# RXTX4.net
KiCad netlist of a schematic drawn in Altium Designer
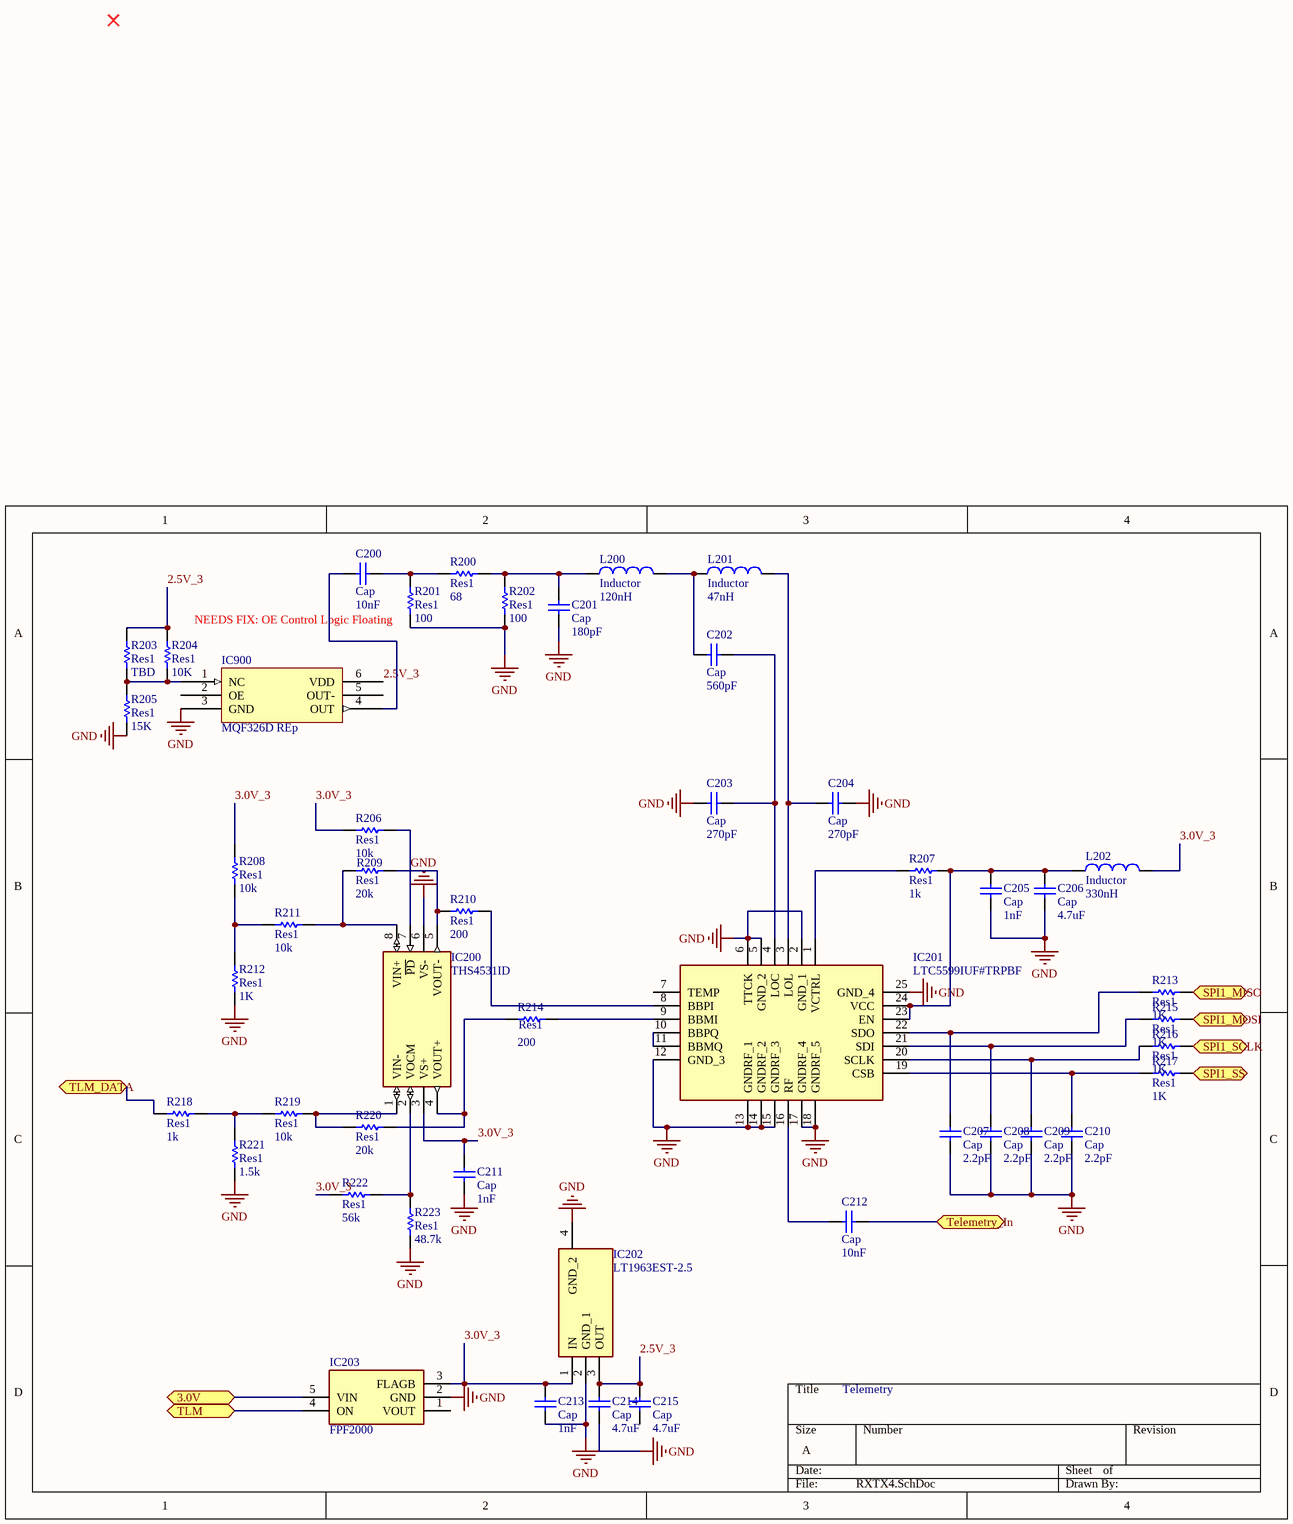
[diagram p0: RXTX4.SchDoc]

(export (version "E")
  (design (tool "Eeschema 10.0.6"))
  (components
    (comp (ref "C200")
      (value "Cap")
      (footprint "0603")
      (description "Capacitor")
      (fields (field (name "ALTIUM_VALUE") "10nF") (field (name "PUBLISHER") "Altium Limited"))
      (libsource (lib "Miscellaneous Devices") (part "Cap"))
    )
    (comp (ref "C201")
      (value "Cap")
      (footprint "0603")
      (description "Capacitor")
      (fields (field (name "ALTIUM_VALUE") "180pF") (field (name "PUBLISHER") "Altium Limited"))
      (libsource (lib "Miscellaneous Devices") (part "Cap"))
    )
    (comp (ref "C202")
      (value "Cap")
      (footprint "0603")
      (description "Capacitor")
      (fields (field (name "ALTIUM_VALUE") "560pF") (field (name "PUBLISHER") "Altium Limited"))
      (libsource (lib "Miscellaneous Devices") (part "Cap"))
    )
    (comp (ref "C203")
      (value "Cap")
      (footprint "0603")
      (description "Capacitor")
      (fields (field (name "ALTIUM_VALUE") "270pF") (field (name "PUBLISHER") "Altium Limited"))
      (libsource (lib "Miscellaneous Devices") (part "Cap"))
    )
    (comp (ref "C204")
      (value "Cap")
      (footprint "0603")
      (description "Capacitor")
      (fields (field (name "ALTIUM_VALUE") "270pF") (field (name "PUBLISHER") "Altium Limited"))
      (libsource (lib "Miscellaneous Devices") (part "Cap"))
    )
    (comp (ref "C205")
      (value "Cap")
      (footprint "0603")
      (description "Capacitor")
      (fields (field (name "ALTIUM_VALUE") "1nF") (field (name "PUBLISHER") "Altium Limited"))
      (libsource (lib "Miscellaneous Devices") (part "Cap"))
    )
    (comp (ref "C206")
      (value "Cap")
      (footprint "0603")
      (description "Capacitor")
      (fields (field (name "ALTIUM_VALUE") "4.7uF") (field (name "PUBLISHER") "Altium Limited"))
      (libsource (lib "Miscellaneous Devices") (part "Cap"))
    )
    (comp (ref "C207")
      (value "Cap")
      (footprint "0603")
      (description "Capacitor")
      (fields (field (name "ALTIUM_VALUE") "2.2pF") (field (name "PUBLISHER") "Altium Limited"))
      (libsource (lib "Miscellaneous Devices") (part "Cap"))
    )
    (comp (ref "C208")
      (value "Cap")
      (footprint "0603")
      (description "Capacitor")
      (fields (field (name "ALTIUM_VALUE") "2.2pF") (field (name "PUBLISHER") "Altium Limited"))
      (libsource (lib "Miscellaneous Devices") (part "Cap"))
    )
    (comp (ref "C209")
      (value "Cap")
      (footprint "0603")
      (description "Capacitor")
      (fields (field (name "ALTIUM_VALUE") "2.2pF") (field (name "PUBLISHER") "Altium Limited"))
      (libsource (lib "Miscellaneous Devices") (part "Cap"))
    )
    (comp (ref "C210")
      (value "Cap")
      (footprint "0603")
      (description "Capacitor")
      (fields (field (name "ALTIUM_VALUE") "2.2pF") (field (name "PUBLISHER") "Altium Limited"))
      (libsource (lib "Miscellaneous Devices") (part "Cap"))
    )
    (comp (ref "C211")
      (value "Cap")
      (footprint "0603")
      (description "Capacitor")
      (fields (field (name "ALTIUM_VALUE") "1nF") (field (name "PUBLISHER") "Altium Limited"))
      (libsource (lib "Miscellaneous Devices") (part "Cap"))
    )
    (comp (ref "C212")
      (value "Cap")
      (footprint "0603")
      (description "Capacitor")
      (fields (field (name "ALTIUM_VALUE") "10nF") (field (name "PUBLISHER") "Altium Limited"))
      (libsource (lib "Miscellaneous Devices") (part "Cap"))
    )
    (comp (ref "C213")
      (value "Cap")
      (footprint "0603")
      (description "Capacitor")
      (fields (field (name "ALTIUM_VALUE") "1nF") (field (name "PUBLISHER") "Altium Limited"))
      (libsource (lib "Miscellaneous Devices") (part "Cap"))
    )
    (comp (ref "C214")
      (value "Cap")
      (footprint "0603")
      (description "Capacitor")
      (fields (field (name "ALTIUM_VALUE") "4.7uF") (field (name "PUBLISHER") "Altium Limited"))
      (libsource (lib "Miscellaneous Devices") (part "Cap"))
    )
    (comp (ref "C215")
      (value "Cap")
      (footprint "0603")
      (description "Capacitor")
      (fields (field (name "ALTIUM_VALUE") "4.7uF") (field (name "PUBLISHER") "Altium Limited"))
      (libsource (lib "Miscellaneous Devices") (part "Cap"))
    )
    (comp (ref "IC200")
      (value "THS4531ID")
      (footprint "SamacSys:SOIC127P600X175-8N")
      (description "Integrated Circuit")
      (fields (field (name "MOUSER PART NUMBER") "595-THS4531ID") (field (name "RS PART NUMBER") "7741408P"))
      (libsource (lib "*") (part "THS4531ID"))
    )
    (comp (ref "IC201")
      (value "LTC5599IUF#TRPBF")
      (footprint "SamacSys:QFN50P400X400X80-25N-D")
      (description "Integrated Circuit")
      (fields (field (name "MOUSER PART NUMBER") "584-LTC5599IUF#TRPBF"))
      (libsource (lib "*") (part "LTC5599IUF#TRPBF"))
    )
    (comp (ref "IC202")
      (value "LT1963EST-2.5")
      (footprint "SamacSys:SOT230P700X180-4N")
      (description "Integrated Circuit")
      (fields (field (name "MOUSER PART NUMBER") "584-LT1963EST-2.5"))
      (libsource (lib "*") (part "LT1963EST-2.5"))
    )
    (comp (ref "IC203")
      (value "FPF2000")
      (footprint "SamacSys:SOT65P210X110-5N")
      (description "Integrated Circuit")
      (fields (field (name "MOUSER PART NUMBER") "512-FPF2000") (field (name "RS PART NUMBER") "6709942P"))
      (libsource (lib "*") (part "FPF2000"))
    )
    (comp (ref "IC900")
      (value "MQF326D REp")
      (footprint "RXTX_PcbLib1:MQF326D")
      (libsource (lib "MQF326D_REP") (part "Component_1"))
    )
    (comp (ref "L200")
      (value "Inductor")
      (footprint "0603")
      (fields (field (name "ALTIUM_VALUE") "120nH") (field (name "PUBLISHER") "Altium Limited"))
      (libsource (lib "Miscellaneous Devices") (part "Inductor"))
    )
    (comp (ref "L201")
      (value "Inductor")
      (footprint "0603")
      (fields (field (name "ALTIUM_VALUE") "47nH") (field (name "PUBLISHER") "Altium Limited"))
      (libsource (lib "Miscellaneous Devices") (part "Inductor"))
    )
    (comp (ref "L202")
      (value "Inductor")
      (footprint "0603")
      (fields (field (name "ALTIUM_VALUE") "330nH") (field (name "PUBLISHER") "Altium Limited"))
      (libsource (lib "Miscellaneous Devices") (part "Inductor"))
    )
    (comp (ref "R200")
      (value "Res1")
      (footprint "0603")
      (description "Resistor")
      (fields (field (name "ALTIUM_VALUE") "68") (field (name "PUBLISHER") "Altium Limited"))
      (libsource (lib "Miscellaneous Devices") (part "Res1"))
    )
    (comp (ref "R201")
      (value "Res1")
      (footprint "0603")
      (description "Resistor")
      (fields (field (name "ALTIUM_VALUE") "100") (field (name "PUBLISHER") "Altium Limited"))
      (libsource (lib "Miscellaneous Devices") (part "Res1"))
    )
    (comp (ref "R202")
      (value "Res1")
      (footprint "0603")
      (description "Resistor")
      (fields (field (name "ALTIUM_VALUE") "100") (field (name "PUBLISHER") "Altium Limited"))
      (libsource (lib "Miscellaneous Devices") (part "Res1"))
    )
    (comp (ref "R203")
      (value "Res1")
      (footprint "0603")
      (description "Resistor")
      (fields (field (name "ALTIUM_VALUE") "TBD") (field (name "PUBLISHER") "Altium Limited"))
      (libsource (lib "Miscellaneous Devices") (part "Res1"))
    )
    (comp (ref "R204")
      (value "Res1")
      (footprint "0603")
      (description "Resistor")
      (fields (field (name "ALTIUM_VALUE") "10K") (field (name "PUBLISHER") "Altium Limited"))
      (libsource (lib "Miscellaneous Devices") (part "Res1"))
    )
    (comp (ref "R205")
      (value "Res1")
      (footprint "0603")
      (description "Resistor")
      (fields (field (name "ALTIUM_VALUE") "15K") (field (name "PUBLISHER") "Altium Limited"))
      (libsource (lib "Miscellaneous Devices") (part "Res1"))
    )
    (comp (ref "R206")
      (value "Res1")
      (footprint "0603")
      (description "Resistor")
      (fields (field (name "ALTIUM_VALUE") "10k") (field (name "PUBLISHER") "Altium Limited"))
      (libsource (lib "Miscellaneous Devices") (part "Res1"))
    )
    (comp (ref "R207")
      (value "Res1")
      (footprint "0603")
      (description "Resistor")
      (fields (field (name "ALTIUM_VALUE") "1k") (field (name "PUBLISHER") "Altium Limited"))
      (libsource (lib "Miscellaneous Devices") (part "Res1"))
    )
    (comp (ref "R208")
      (value "Res1")
      (footprint "0603")
      (description "Resistor")
      (fields (field (name "ALTIUM_VALUE") "10k") (field (name "PUBLISHER") "Altium Limited"))
      (libsource (lib "Miscellaneous Devices") (part "Res1"))
    )
    (comp (ref "R209")
      (value "Res1")
      (footprint "0603")
      (description "Resistor")
      (fields (field (name "ALTIUM_VALUE") "20k") (field (name "PUBLISHER") "Altium Limited"))
      (libsource (lib "Miscellaneous Devices") (part "Res1"))
    )
    (comp (ref "R210")
      (value "Res1")
      (footprint "0603")
      (description "Resistor")
      (fields (field (name "ALTIUM_VALUE") "200") (field (name "PUBLISHER") "Altium Limited"))
      (libsource (lib "Miscellaneous Devices") (part "Res1"))
    )
    (comp (ref "R211")
      (value "Res1")
      (footprint "0603")
      (description "Resistor")
      (fields (field (name "ALTIUM_VALUE") "10k") (field (name "PUBLISHER") "Altium Limited"))
      (libsource (lib "Miscellaneous Devices") (part "Res1"))
    )
    (comp (ref "R212")
      (value "Res1")
      (footprint "0603")
      (description "Resistor")
      (fields (field (name "ALTIUM_VALUE") "1K") (field (name "PUBLISHER") "Altium Limited"))
      (libsource (lib "Miscellaneous Devices") (part "Res1"))
    )
    (comp (ref "R213")
      (value "Res1")
      (footprint "0603")
      (description "Resistor")
      (fields (field (name "ALTIUM_VALUE") "1K") (field (name "PUBLISHER") "Altium Limited"))
      (libsource (lib "Miscellaneous Devices") (part "Res1"))
    )
    (comp (ref "R214")
      (value "Res1")
      (footprint "0603")
      (description "Resistor")
      (fields (field (name "ALTIUM_VALUE") "200") (field (name "PUBLISHER") "Altium Limited"))
      (libsource (lib "Miscellaneous Devices") (part "Res1"))
    )
    (comp (ref "R215")
      (value "Res1")
      (footprint "0603")
      (description "Resistor")
      (fields (field (name "ALTIUM_VALUE") "1K") (field (name "PUBLISHER") "Altium Limited"))
      (libsource (lib "Miscellaneous Devices") (part "Res1"))
    )
    (comp (ref "R216")
      (value "Res1")
      (footprint "0603")
      (description "Resistor")
      (fields (field (name "ALTIUM_VALUE") "1K") (field (name "PUBLISHER") "Altium Limited"))
      (libsource (lib "Miscellaneous Devices") (part "Res1"))
    )
    (comp (ref "R217")
      (value "Res1")
      (footprint "0603")
      (description "Resistor")
      (fields (field (name "ALTIUM_VALUE") "1K") (field (name "PUBLISHER") "Altium Limited"))
      (libsource (lib "Miscellaneous Devices") (part "Res1"))
    )
    (comp (ref "R218")
      (value "Res1")
      (footprint "0603")
      (description "Resistor")
      (fields (field (name "ALTIUM_VALUE") "1k") (field (name "PUBLISHER") "Altium Limited"))
      (libsource (lib "Miscellaneous Devices") (part "Res1"))
    )
    (comp (ref "R219")
      (value "Res1")
      (footprint "0603")
      (description "Resistor")
      (fields (field (name "ALTIUM_VALUE") "10k") (field (name "PUBLISHER") "Altium Limited"))
      (libsource (lib "Miscellaneous Devices") (part "Res1"))
    )
    (comp (ref "R220")
      (value "Res1")
      (footprint "0603")
      (description "Resistor")
      (fields (field (name "ALTIUM_VALUE") "20k") (field (name "PUBLISHER") "Altium Limited"))
      (libsource (lib "Miscellaneous Devices") (part "Res1"))
    )
    (comp (ref "R221")
      (value "Res1")
      (footprint "0603")
      (description "Resistor")
      (fields (field (name "ALTIUM_VALUE") "1.5k") (field (name "PUBLISHER") "Altium Limited"))
      (libsource (lib "Miscellaneous Devices") (part "Res1"))
    )
    (comp (ref "R222")
      (value "Res1")
      (footprint "0603")
      (description "Resistor")
      (fields (field (name "ALTIUM_VALUE") "56k") (field (name "PUBLISHER") "Altium Limited"))
      (libsource (lib "Miscellaneous Devices") (part "Res1"))
    )
    (comp (ref "R223")
      (value "Res1")
      (footprint "0603")
      (description "Resistor")
      (fields (field (name "ALTIUM_VALUE") "48.7k") (field (name "PUBLISHER") "Altium Limited"))
      (libsource (lib "Miscellaneous Devices") (part "Res1"))
    )
  )
  (nets
    (net (code "1") (name "/2.5V_3") (class "Default")
      (node (ref "C214") (pin "1") (pinfunction "1_1") (pintype "passive"))
      (node (ref "C215") (pin "1") (pinfunction "1_1") (pintype "passive"))
      (node (ref "IC202") (pin "3") (pinfunction "OUT_3") (pintype "passive"))
      (node (ref "IC900") (pin "6") (pinfunction "VDD_6") (pintype "power_in"))
      (node (ref "R203") (pin "2") (pinfunction "2_2") (pintype "passive"))
      (node (ref "R204") (pin "2") (pinfunction "2_2") (pintype "passive"))
    )
    (net (code "2") (name "/3.0V") (class "Default")
      (node (ref "IC203") (pin "5") (pinfunction "VIN_5") (pintype "passive"))
    )
    (net (code "3") (name "/3.0V_3") (class "Default")
      (node (ref "C211") (pin "1") (pinfunction "1_1") (pintype "passive"))
      (node (ref "C213") (pin "1") (pinfunction "1_1") (pintype "passive"))
      (node (ref "IC200") (pin "3") (pinfunction "VS+_3") (pintype "power_in"))
      (node (ref "IC202") (pin "1") (pinfunction "IN_1") (pintype "passive"))
      (node (ref "IC203") (pin "3") (pinfunction "FLAGB_3") (pintype "passive"))
      (node (ref "L202") (pin "2") (pinfunction "2_2") (pintype "passive"))
      (node (ref "R206") (pin "1") (pinfunction "1_1") (pintype "passive"))
      (node (ref "R208") (pin "1") (pinfunction "1_1") (pintype "passive"))
      (node (ref "R222") (pin "1") (pinfunction "1_1") (pintype "passive"))
    )
    (net (code "4") (name "/SPI1_MISO") (class "Default")
      (node (ref "R213") (pin "2") (pinfunction "2_2") (pintype "passive"))
    )
    (net (code "5") (name "/SPI1_MOSI") (class "Default")
      (node (ref "R215") (pin "2") (pinfunction "2_2") (pintype "passive"))
    )
    (net (code "6") (name "/SPI1_SCLK") (class "Default")
      (node (ref "R216") (pin "2") (pinfunction "2_2") (pintype "passive"))
    )
    (net (code "7") (name "/SPI1_SS") (class "Default")
      (node (ref "R217") (pin "2") (pinfunction "2_2") (pintype "passive"))
    )
    (net (code "8") (name "/TLM") (class "Default")
      (node (ref "IC203") (pin "4") (pinfunction "ON_4") (pintype "passive"))
    )
    (net (code "9") (name "/TLM_DATA") (class "Default")
      (node (ref "R218") (pin "1") (pinfunction "1_1") (pintype "passive"))
    )
    (net (code "10") (name "/Telemetry_In") (class "Default")
      (node (ref "C212") (pin "2") (pinfunction "2_2") (pintype "passive"))
    )
    (net (code "11") (name "GND") (class "Default")
      (node (ref "C201") (pin "1") (pinfunction "1_1") (pintype "passive"))
      (node (ref "C203") (pin "2") (pinfunction "2_2") (pintype "passive"))
      (node (ref "C204") (pin "1") (pinfunction "1_1") (pintype "passive"))
      (node (ref "C205") (pin "2") (pinfunction "2_2") (pintype "passive"))
      (node (ref "C206") (pin "2") (pinfunction "2_2") (pintype "passive"))
      (node (ref "C207") (pin "2") (pinfunction "2_2") (pintype "passive"))
      (node (ref "C208") (pin "2") (pinfunction "2_2") (pintype "passive"))
      (node (ref "C209") (pin "2") (pinfunction "2_2") (pintype "passive"))
      (node (ref "C210") (pin "2") (pinfunction "2_2") (pintype "passive"))
      (node (ref "C211") (pin "2") (pinfunction "2_2") (pintype "passive"))
      (node (ref "C213") (pin "2") (pinfunction "2_2") (pintype "passive"))
      (node (ref "C214") (pin "2") (pinfunction "2_2") (pintype "passive"))
      (node (ref "IC200") (pin "6") (pinfunction "VS-_6") (pintype "power_in"))
      (node (ref "IC201") (pin "12") (pinfunction "GND_3_12") (pintype "passive"))
      (node (ref "IC201") (pin "13") (pinfunction "GNDRF_1_13") (pintype "passive"))
      (node (ref "IC201") (pin "14") (pinfunction "GNDRF_2_14") (pintype "passive"))
      (node (ref "IC201") (pin "15") (pinfunction "GNDRF_3_15") (pintype "passive"))
      (node (ref "IC201") (pin "17") (pinfunction "GNDRF_4_17") (pintype "passive"))
      (node (ref "IC201") (pin "18") (pinfunction "GNDRF_5_18") (pintype "passive"))
      (node (ref "IC201") (pin "2") (pinfunction "GND_1_2") (pintype "passive"))
      (node (ref "IC201") (pin "25") (pinfunction "GND_4_25") (pintype "passive"))
      (node (ref "IC201") (pin "5") (pinfunction "GND_2_5") (pintype "passive"))
      (node (ref "IC201") (pin "6") (pinfunction "TTCK_6") (pintype "passive"))
      (node (ref "IC202") (pin "2") (pinfunction "GND_1_2") (pintype "passive"))
      (node (ref "IC202") (pin "4") (pinfunction "GND_2_4") (pintype "passive"))
      (node (ref "IC203") (pin "2") (pinfunction "GND_2") (pintype "passive"))
      (node (ref "IC900") (pin "3") (pinfunction "GND_3") (pintype "power_in"))
      (node (ref "R201") (pin "1") (pinfunction "1_1") (pintype "passive"))
      (node (ref "R202") (pin "2") (pinfunction "2_2") (pintype "passive"))
      (node (ref "R205") (pin "1") (pinfunction "1_1") (pintype "passive"))
      (node (ref "R212") (pin "2") (pinfunction "2_2") (pintype "passive"))
      (node (ref "R221") (pin "1") (pinfunction "1_1") (pintype "passive"))
      (node (ref "R223") (pin "1") (pinfunction "1_1") (pintype "passive"))
    )
    (net (code "12") (name "Net-(C200-Pad2)") (class "Default")
      (node (ref "C200") (pin "2") (pinfunction "2_2") (pintype "passive"))
      (node (ref "R200") (pin "2") (pinfunction "2_2") (pintype "passive"))
      (node (ref "R201") (pin "2") (pinfunction "2_2") (pintype "passive"))
    )
    (net (code "13") (name "Net-(C201-Pad2)") (class "Default")
      (node (ref "C201") (pin "2") (pinfunction "2_2") (pintype "passive"))
      (node (ref "L200") (pin "1") (pinfunction "1_1") (pintype "passive"))
      (node (ref "R200") (pin "1") (pinfunction "1_1") (pintype "passive"))
      (node (ref "R202") (pin "1") (pinfunction "1_1") (pintype "passive"))
    )
    (net (code "14") (name "Net-(C202-Pad2)") (class "Default")
      (node (ref "C202") (pin "2") (pinfunction "2_2") (pintype "passive"))
      (node (ref "L200") (pin "2") (pinfunction "2_2") (pintype "passive"))
      (node (ref "L201") (pin "1") (pinfunction "1_1") (pintype "passive"))
    )
    (net (code "15") (name "Net-(IC200-VIN+)") (class "Default")
      (node (ref "IC200") (pin "8") (pinfunction "VIN+_8") (pintype "bidirectional"))
      (node (ref "R209") (pin "1") (pinfunction "1_1") (pintype "passive"))
      (node (ref "R211") (pin "2") (pinfunction "2_2") (pintype "passive"))
    )
    (net (code "16") (name "Net-(IC200-VIN-)") (class "Default")
      (node (ref "IC200") (pin "1") (pinfunction "VIN-_1") (pintype "bidirectional"))
      (node (ref "R219") (pin "2") (pinfunction "2_2") (pintype "passive"))
      (node (ref "R220") (pin "1") (pinfunction "1_1") (pintype "passive"))
    )
    (net (code "17") (name "Net-(IC200-VOCM)") (class "Default")
      (node (ref "IC200") (pin "2") (pinfunction "VOCM_2") (pintype "bidirectional"))
      (node (ref "R222") (pin "2") (pinfunction "2_2") (pintype "passive"))
      (node (ref "R223") (pin "2") (pinfunction "2_2") (pintype "passive"))
    )
    (net (code "18") (name "Net-(IC200-VOUT+)") (class "Default")
      (node (ref "IC200") (pin "4") (pinfunction "VOUT+_4") (pintype "output"))
      (node (ref "R214") (pin "1") (pinfunction "1_1") (pintype "passive"))
      (node (ref "R220") (pin "2") (pinfunction "2_2") (pintype "passive"))
    )
    (net (code "19") (name "Net-(IC200-VOUT-)") (class "Default")
      (node (ref "IC200") (pin "5") (pinfunction "VOUT-_5") (pintype "output"))
      (node (ref "R209") (pin "2") (pinfunction "2_2") (pintype "passive"))
      (node (ref "R210") (pin "1") (pinfunction "1_1") (pintype "passive"))
    )
    (net (code "20") (name "Net-(IC200-~{PD})") (class "Default")
      (node (ref "IC200") (pin "7") (pinfunction "~{PD}_7") (pintype "input"))
      (node (ref "R206") (pin "2") (pinfunction "2_2") (pintype "passive"))
    )
    (net (code "21") (name "Net-(IC201-BBMI)") (class "Default")
      (node (ref "IC201") (pin "9") (pinfunction "BBMI_9") (pintype "passive"))
      (node (ref "R214") (pin "2") (pinfunction "2_2") (pintype "passive"))
    )
    (net (code "22") (name "Net-(IC201-BBMQ)") (class "Default")
      (node (ref "IC201") (pin "10") (pinfunction "BBPQ_10") (pintype "passive"))
      (node (ref "IC201") (pin "11") (pinfunction "BBMQ_11") (pintype "passive"))
    )
    (net (code "23") (name "Net-(IC201-BBPI)") (class "Default")
      (node (ref "IC201") (pin "8") (pinfunction "BBPI_8") (pintype "passive"))
      (node (ref "R210") (pin "2") (pinfunction "2_2") (pintype "passive"))
    )
    (net (code "24") (name "Net-(IC201-CSB)") (class "Default")
      (node (ref "C210") (pin "1") (pinfunction "1_1") (pintype "passive"))
      (node (ref "IC201") (pin "19") (pinfunction "CSB_19") (pintype "passive"))
      (node (ref "R217") (pin "1") (pinfunction "1_1") (pintype "passive"))
    )
    (net (code "25") (name "Net-(IC201-EN)") (class "Default")
      (node (ref "C205") (pin "1") (pinfunction "1_1") (pintype "passive"))
      (node (ref "C206") (pin "1") (pinfunction "1_1") (pintype "passive"))
      (node (ref "IC201") (pin "23") (pinfunction "EN_23") (pintype "passive"))
      (node (ref "IC201") (pin "24") (pinfunction "VCC_24") (pintype "passive"))
      (node (ref "L202") (pin "1") (pinfunction "1_1") (pintype "passive"))
      (node (ref "R207") (pin "1") (pinfunction "1_1") (pintype "passive"))
    )
    (net (code "26") (name "Net-(IC201-LOC)") (class "Default")
      (node (ref "C202") (pin "1") (pinfunction "1_1") (pintype "passive"))
      (node (ref "C203") (pin "1") (pinfunction "1_1") (pintype "passive"))
      (node (ref "IC201") (pin "4") (pinfunction "LOC_4") (pintype "passive"))
    )
    (net (code "27") (name "Net-(IC201-LOL)") (class "Default")
      (node (ref "C204") (pin "2") (pinfunction "2_2") (pintype "passive"))
      (node (ref "IC201") (pin "3") (pinfunction "LOL_3") (pintype "passive"))
      (node (ref "L201") (pin "2") (pinfunction "2_2") (pintype "passive"))
    )
    (net (code "28") (name "Net-(IC201-RF)") (class "Default")
      (node (ref "C212") (pin "1") (pinfunction "1_1") (pintype "passive"))
      (node (ref "IC201") (pin "16") (pinfunction "RF_16") (pintype "passive"))
    )
    (net (code "29") (name "Net-(IC201-SCLK)") (class "Default")
      (node (ref "C209") (pin "1") (pinfunction "1_1") (pintype "passive"))
      (node (ref "IC201") (pin "20") (pinfunction "SCLK_20") (pintype "passive"))
      (node (ref "R216") (pin "1") (pinfunction "1_1") (pintype "passive"))
    )
    (net (code "30") (name "Net-(IC201-SDI)") (class "Default")
      (node (ref "C208") (pin "1") (pinfunction "1_1") (pintype "passive"))
      (node (ref "IC201") (pin "21") (pinfunction "SDI_21") (pintype "passive"))
      (node (ref "R215") (pin "1") (pinfunction "1_1") (pintype "passive"))
    )
    (net (code "31") (name "Net-(IC201-SDO)") (class "Default")
      (node (ref "C207") (pin "1") (pinfunction "1_1") (pintype "passive"))
      (node (ref "IC201") (pin "22") (pinfunction "SDO_22") (pintype "passive"))
      (node (ref "R213") (pin "1") (pinfunction "1_1") (pintype "passive"))
    )
    (net (code "32") (name "Net-(IC201-VCTRL)") (class "Default")
      (node (ref "IC201") (pin "1") (pinfunction "VCTRL_1") (pintype "passive"))
      (node (ref "R207") (pin "2") (pinfunction "2_2") (pintype "passive"))
    )
    (net (code "33") (name "Net-(IC900-NC)") (class "Default")
      (node (ref "IC900") (pin "1") (pinfunction "NC_1") (pintype "input"))
      (node (ref "R203") (pin "1") (pinfunction "1_1") (pintype "passive"))
      (node (ref "R204") (pin "1") (pinfunction "1_1") (pintype "passive"))
      (node (ref "R205") (pin "2") (pinfunction "2_2") (pintype "passive"))
    )
    (net (code "34") (name "Net-(IC900-OUT)") (class "Default")
      (node (ref "C200") (pin "1") (pinfunction "1_1") (pintype "passive"))
      (node (ref "IC900") (pin "4") (pinfunction "OUT_4") (pintype "output"))
    )
    (net (code "35") (name "Net-(R208-Pad2)") (class "Default")
      (node (ref "R208") (pin "2") (pinfunction "2_2") (pintype "passive"))
      (node (ref "R211") (pin "1") (pinfunction "1_1") (pintype "passive"))
      (node (ref "R212") (pin "1") (pinfunction "1_1") (pintype "passive"))
    )
    (net (code "36") (name "Net-(R218-Pad2)") (class "Default")
      (node (ref "R218") (pin "2") (pinfunction "2_2") (pintype "passive"))
      (node (ref "R219") (pin "1") (pinfunction "1_1") (pintype "passive"))
      (node (ref "R221") (pin "2") (pinfunction "2_2") (pintype "passive"))
    )
    (net (code "37") (name "unconnected-(C215-Pad2)") (class "Default")
      (node (ref "C215") (pin "2") (pinfunction "2_2") (pintype "passive"))
    )
    (net (code "38") (name "unconnected-(IC201-TEMP-Pad7)") (class "Default")
      (node (ref "IC201") (pin "7") (pinfunction "TEMP_7") (pintype "passive"))
    )
    (net (code "39") (name "unconnected-(IC203-VOUT-Pad1)") (class "Default")
      (node (ref "IC203") (pin "1") (pinfunction "VOUT_1") (pintype "passive"))
    )
    (net (code "40") (name "unconnected-(IC900-OE-Pad2)") (class "Default")
      (node (ref "IC900") (pin "2") (pinfunction "OE_2") (pintype "passive"))
    )
    (net (code "41") (name "unconnected-(IC900-OUT--Pad5)") (class "Default")
      (node (ref "IC900") (pin "5") (pinfunction "OUT-_5") (pintype "passive"))
    )
  )
)
